# xboard.net
KiCad netlist of a schematic drawn in EAGLE
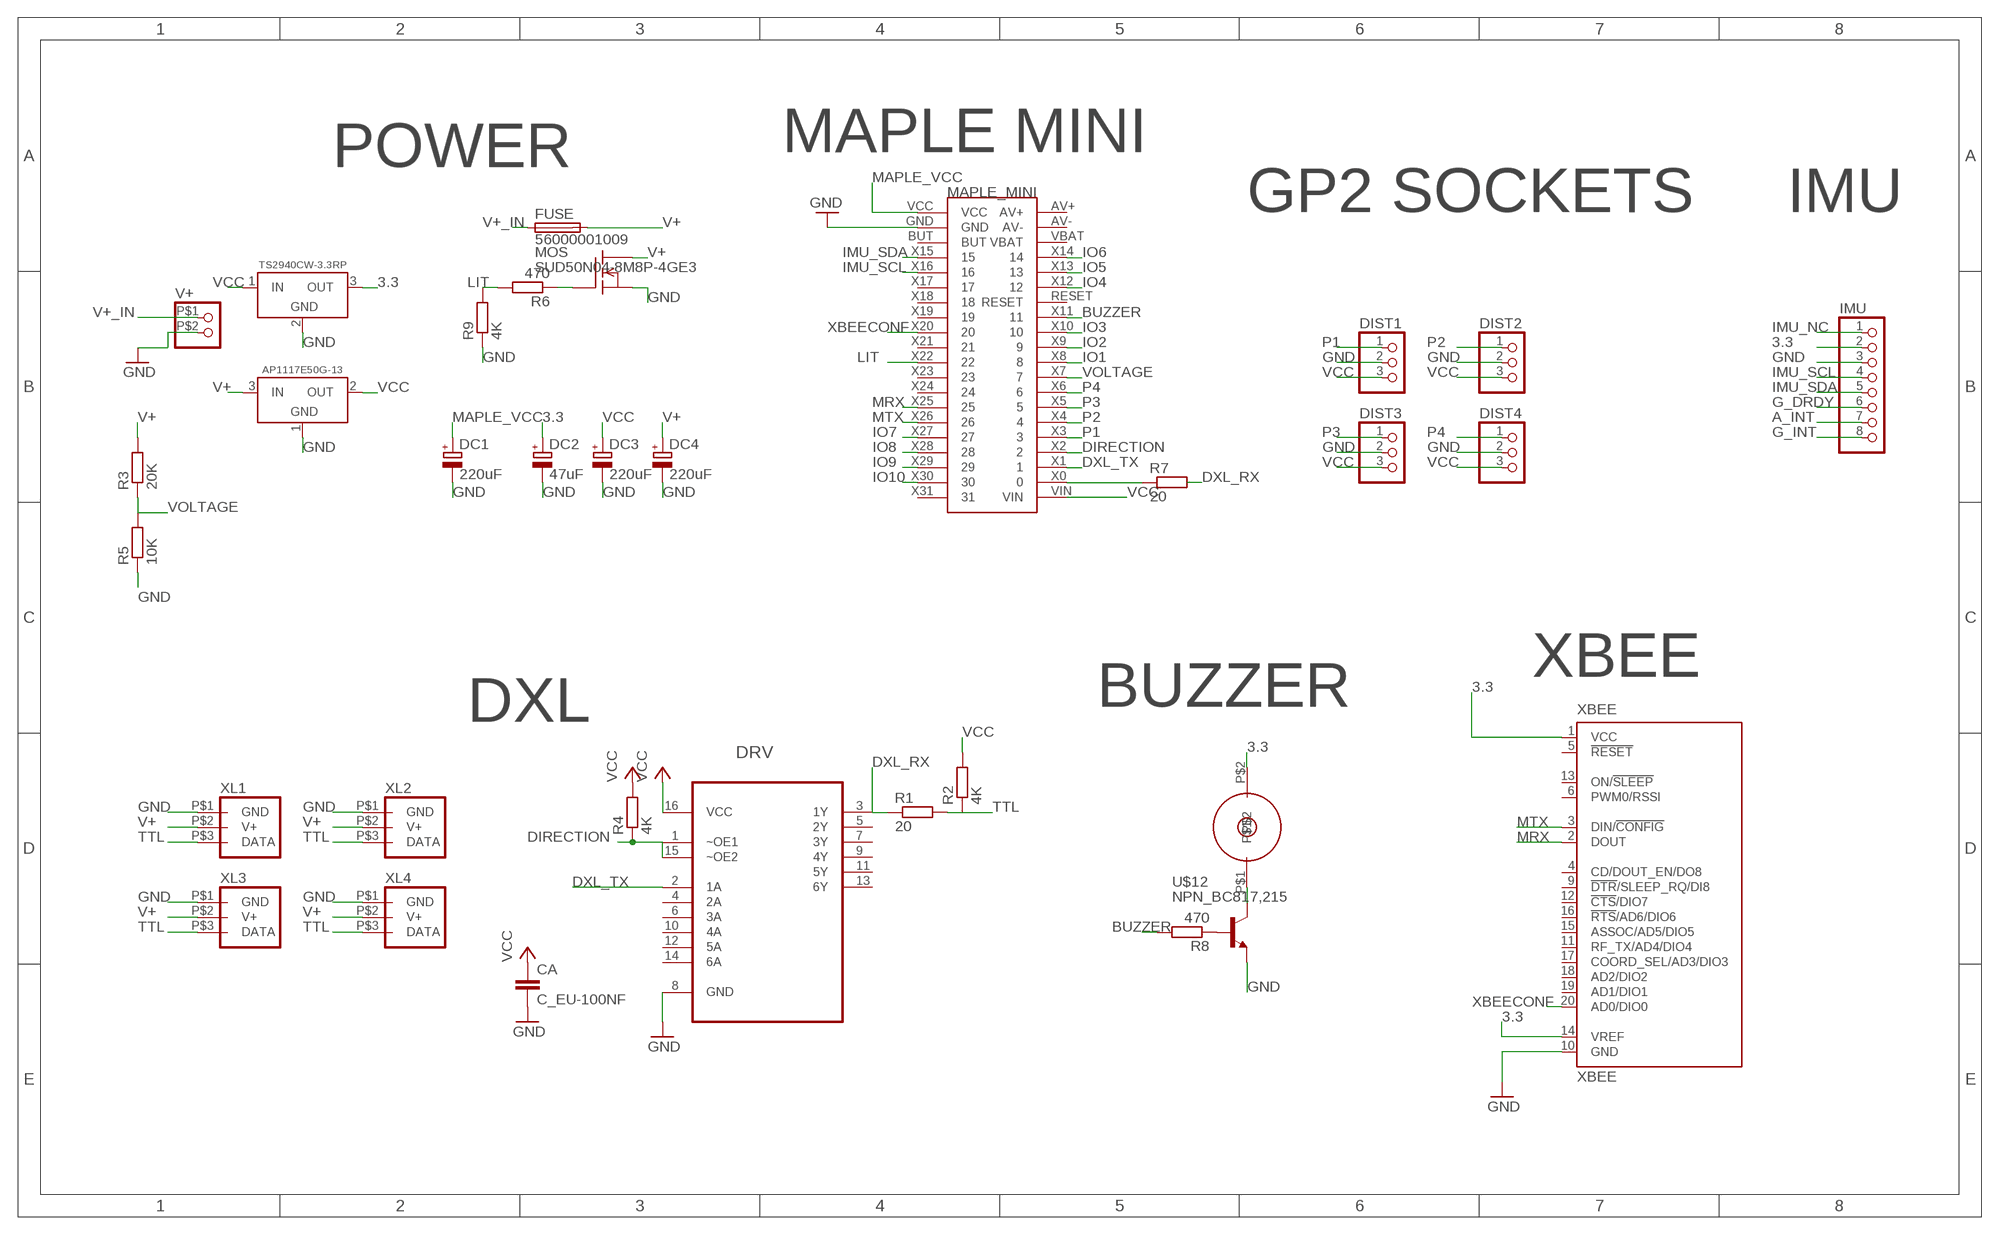
[diagram p0: schematic, sheet 1]

(export (version "E")
  (design (tool "Eeschema 10.0.6"))
  (components
    (comp (ref "BUZZER")
      (value "BUZZER66")
      (footprint "eagle-import:BUZZER66")
      (libsource (lib "eagle-import") (part "BUZZER66"))
    )
    (comp (ref "CA")
      (value "C_EU-100NF")
      (footprint "eagle-import:C0805")
      (libsource (lib "eagle-import") (part "C_EU-100NF"))
    )
    (comp (ref "DC1")
      (value "220uF")
      (footprint "eagle-import:PANASONIC_D8")
      (libsource (lib "eagle-import") (part "CPOL_EUPANASONIC_D8"))
    )
    (comp (ref "DC2")
      (value "47uF")
      (footprint "eagle-import:PANASONIC_D")
      (libsource (lib "eagle-import") (part "CPOL_EUPANASONIC_D"))
    )
    (comp (ref "DC3")
      (value "220uF")
      (footprint "eagle-import:PANASONIC_D8")
      (libsource (lib "eagle-import") (part "CPOL_EUPANASONIC_D8"))
    )
    (comp (ref "DC4")
      (value "220uF")
      (footprint "eagle-import:PANASONIC_D8")
      (libsource (lib "eagle-import") (part "CPOL_EUPANASONIC_D8"))
    )
    (comp (ref "DIST1")
      (value "CONNEC_1X03")
      (footprint "eagle-import:CONNEC_1X03")
      (libsource (lib "eagle-import") (part "CONNEC_1X03"))
    )
    (comp (ref "DIST2")
      (value "CONNEC_1X03")
      (footprint "eagle-import:CONNEC_1X03")
      (libsource (lib "eagle-import") (part "CONNEC_1X03"))
    )
    (comp (ref "DIST3")
      (value "CONNEC_1X03")
      (footprint "eagle-import:CONNEC_1X03")
      (libsource (lib "eagle-import") (part "CONNEC_1X03"))
    )
    (comp (ref "DIST4")
      (value "CONNEC_1X03")
      (footprint "eagle-import:CONNEC_1X03")
      (libsource (lib "eagle-import") (part "CONNEC_1X03"))
    )
    (comp (ref "DRV")
      (value "CD74HCT367M")
      (footprint "eagle-import:SOIC127P600X175-16N")
      (libsource (lib "eagle-import") (part "CD74HCT367M"))
    )
    (comp (ref "FUSE")
      (value "56000001009")
      (footprint "eagle-import:56000001009")
      (libsource (lib "eagle-import") (part "56000001009"))
    )
    (comp (ref "IMU")
      (value "CONNEC_1X08")
      (footprint "eagle-import:CONNEC_1X08")
      (libsource (lib "eagle-import") (part "CONNEC_1X08"))
    )
    (comp (ref "MAPLE_MINI")
      (value "MAPLE_MINI")
      (footprint "eagle-import:CONNEC_2X20")
      (libsource (lib "eagle-import") (part "MAPLE_MINI"))
    )
    (comp (ref "MOS")
      (value "SUD50N04-8M8P-4GE3")
      (footprint "eagle-import:TO252")
      (libsource (lib "eagle-import") (part "SUD50N04-8M8P-4GE3"))
    )
    (comp (ref "R1")
      (value "20")
      (footprint "eagle-import:R0805")
      (libsource (lib "eagle-import") (part "R-EU_R0805"))
    )
    (comp (ref "R2")
      (value "4K")
      (footprint "eagle-import:R0805")
      (libsource (lib "eagle-import") (part "R-EU_R0805"))
    )
    (comp (ref "R3")
      (value "20K")
      (footprint "eagle-import:R0805")
      (libsource (lib "eagle-import") (part "R-EU_R0805"))
    )
    (comp (ref "R4")
      (value "4K")
      (footprint "eagle-import:R0805")
      (libsource (lib "eagle-import") (part "RESISTANCE-R0805"))
    )
    (comp (ref "R5")
      (value "10K")
      (footprint "eagle-import:R0805")
      (libsource (lib "eagle-import") (part "R-EU_R0805"))
    )
    (comp (ref "R6")
      (value "470")
      (footprint "eagle-import:R0805")
      (libsource (lib "eagle-import") (part "R-EU_R0805"))
    )
    (comp (ref "R7")
      (value "20")
      (footprint "eagle-import:R0805")
      (libsource (lib "eagle-import") (part "R-EU_R0805"))
    )
    (comp (ref "R8")
      (value "470")
      (footprint "eagle-import:R0805")
      (libsource (lib "eagle-import") (part "R-EU_R0805"))
    )
    (comp (ref "R9")
      (value "4K")
      (footprint "eagle-import:R0805")
      (libsource (lib "eagle-import") (part "RESISTANCE-R0805"))
    )
    (comp (ref "U$7")
      (value "TS2940CW-3.3RP")
      (footprint "eagle-import:SOT223")
      (libsource (lib "eagle-import") (part "TS2940CW-3.3RP"))
    )
    (comp (ref "U$8")
      (value "AP1117E50G-13")
      (footprint "eagle-import:SOT223")
      (libsource (lib "eagle-import") (part "AP1117E50G-13"))
    )
    (comp (ref "U$12")
      (value "NPN_BC817,215")
      (footprint "eagle-import:SOT-23")
      (libsource (lib "eagle-import") (part "NPN_BC817,215"))
    )
    (comp (ref "V+")
      (value "CONNEC_1X02BIG")
      (footprint "eagle-import:CONNEC_1X02_BIG")
      (libsource (lib "eagle-import") (part "CONNEC_1X02BIG"))
    )
    (comp (ref "XBEE")
      (value "XBEE")
      (footprint "eagle-import:XBEE")
      (fields (field (name "MPN") "XBP24-Z7UIT-004"))
      (libsource (lib "eagle-import") (part "XBEE"))
    )
    (comp (ref "XL1")
      (value "XL_320_CONNEC")
      (footprint "eagle-import:DXL_320_CONNEC")
      (libsource (lib "eagle-import") (part "XL_320_CONNEC"))
    )
    (comp (ref "XL2")
      (value "XL_320_CONNEC")
      (footprint "eagle-import:DXL_320_CONNEC")
      (libsource (lib "eagle-import") (part "XL_320_CONNEC"))
    )
    (comp (ref "XL3")
      (value "XL_320_CONNEC")
      (footprint "eagle-import:DXL_320_CONNEC")
      (libsource (lib "eagle-import") (part "XL_320_CONNEC"))
    )
    (comp (ref "XL4")
      (value "XL_320_CONNEC")
      (footprint "eagle-import:DXL_320_CONNEC")
      (libsource (lib "eagle-import") (part "XL_320_CONNEC"))
    )
  )
  (nets
    (net (code "1") (name "/3.3") (class "Default")
      (node (ref "BUZZER") (pin "P$2") (pinfunction "P$2_P$2") (pintype "bidirectional"))
      (node (ref "DC2") (pin "+") (pinfunction "+_+") (pintype "passive"))
      (node (ref "IMU") (pin "2") (pinfunction "2_2") (pintype "passive"))
      (node (ref "U$7") (pin "3") (pinfunction "OUT_3") (pintype "output"))
      (node (ref "XBEE") (pin "1") (pinfunction "VCC_1") (pintype "power_in"))
      (node (ref "XBEE") (pin "14") (pinfunction "VREF_14") (pintype "input"))
    )
    (net (code "2") (name "/A_INT") (class "Default")
      (node (ref "IMU") (pin "7") (pinfunction "7_7") (pintype "passive"))
    )
    (net (code "3") (name "/BUZZER") (class "Default")
      (node (ref "MAPLE_MINI") (pin "X11") (pinfunction "11_X11") (pintype "bidirectional"))
      (node (ref "R8") (pin "2") (pinfunction "2_2") (pintype "passive"))
    )
    (net (code "4") (name "/DIRECTION") (class "Default")
      (node (ref "DRV") (pin "1") (pinfunction "~{OE1}_1") (pintype "input"))
      (node (ref "DRV") (pin "15") (pinfunction "~{OE2}_15") (pintype "input"))
      (node (ref "MAPLE_MINI") (pin "X2") (pinfunction "2_X2") (pintype "bidirectional"))
      (node (ref "R4") (pin "1") (pinfunction "1_1") (pintype "passive"))
    )
    (net (code "5") (name "/DXL_RX") (class "Default")
      (node (ref "DRV") (pin "3") (pinfunction "1Y_3") (pintype "output"))
      (node (ref "R1") (pin "1") (pinfunction "1_1") (pintype "passive"))
      (node (ref "R7") (pin "2") (pinfunction "2_2") (pintype "passive"))
    )
    (net (code "6") (name "/DXL_TX") (class "Default")
      (node (ref "DRV") (pin "2") (pinfunction "1A_2") (pintype "input"))
      (node (ref "MAPLE_MINI") (pin "X1") (pinfunction "1_X1") (pintype "bidirectional"))
    )
    (net (code "7") (name "/G_DRDY") (class "Default")
      (node (ref "IMU") (pin "6") (pinfunction "6_6") (pintype "passive"))
    )
    (net (code "8") (name "/G_INT") (class "Default")
      (node (ref "IMU") (pin "8") (pinfunction "8_8") (pintype "passive"))
    )
    (net (code "9") (name "/IMU_NC") (class "Default")
      (node (ref "IMU") (pin "1") (pinfunction "1_1") (pintype "passive"))
    )
    (net (code "10") (name "/IMU_SCL") (class "Default")
      (node (ref "IMU") (pin "4") (pinfunction "4_4") (pintype "passive"))
      (node (ref "MAPLE_MINI") (pin "X16") (pinfunction "16_X16") (pintype "bidirectional"))
    )
    (net (code "11") (name "/IMU_SDA") (class "Default")
      (node (ref "IMU") (pin "5") (pinfunction "5_5") (pintype "passive"))
      (node (ref "MAPLE_MINI") (pin "X15") (pinfunction "15_X15") (pintype "bidirectional"))
    )
    (net (code "12") (name "/IO1") (class "Default")
      (node (ref "MAPLE_MINI") (pin "X8") (pinfunction "8_X8") (pintype "bidirectional"))
    )
    (net (code "13") (name "/IO2") (class "Default")
      (node (ref "MAPLE_MINI") (pin "X9") (pinfunction "9_X9") (pintype "bidirectional"))
    )
    (net (code "14") (name "/IO3") (class "Default")
      (node (ref "MAPLE_MINI") (pin "X10") (pinfunction "10_X10") (pintype "bidirectional"))
    )
    (net (code "15") (name "/IO4") (class "Default")
      (node (ref "MAPLE_MINI") (pin "X12") (pinfunction "12_X12") (pintype "bidirectional"))
    )
    (net (code "16") (name "/IO5") (class "Default")
      (node (ref "MAPLE_MINI") (pin "X13") (pinfunction "13_X13") (pintype "bidirectional"))
    )
    (net (code "17") (name "/IO6") (class "Default")
      (node (ref "MAPLE_MINI") (pin "X14") (pinfunction "14_X14") (pintype "bidirectional"))
    )
    (net (code "18") (name "/IO7") (class "Default")
      (node (ref "MAPLE_MINI") (pin "X27") (pinfunction "27_X27") (pintype "bidirectional"))
    )
    (net (code "19") (name "/IO8") (class "Default")
      (node (ref "MAPLE_MINI") (pin "X28") (pinfunction "28_X28") (pintype "bidirectional"))
    )
    (net (code "20") (name "/IO9") (class "Default")
      (node (ref "MAPLE_MINI") (pin "X29") (pinfunction "29_X29") (pintype "bidirectional"))
    )
    (net (code "21") (name "/IO10") (class "Default")
      (node (ref "MAPLE_MINI") (pin "X30") (pinfunction "30_X30") (pintype "bidirectional"))
    )
    (net (code "22") (name "/LIT") (class "Default")
      (node (ref "MAPLE_MINI") (pin "X22") (pinfunction "22_X22") (pintype "bidirectional"))
      (node (ref "R6") (pin "2") (pinfunction "2_2") (pintype "passive"))
      (node (ref "R9") (pin "2") (pinfunction "2_2") (pintype "passive"))
    )
    (net (code "23") (name "/MAPLE_VCC") (class "Default")
      (node (ref "DC1") (pin "+") (pinfunction "+_+") (pintype "passive"))
      (node (ref "MAPLE_MINI") (pin "VCC") (pinfunction "VCC_VCC") (pintype "bidirectional"))
    )
    (net (code "24") (name "/MRX") (class "Default")
      (node (ref "MAPLE_MINI") (pin "X25") (pinfunction "25_X25") (pintype "bidirectional"))
      (node (ref "XBEE") (pin "2") (pinfunction "DOUT_2") (pintype "output"))
    )
    (net (code "25") (name "/MTX") (class "Default")
      (node (ref "MAPLE_MINI") (pin "X26") (pinfunction "26_X26") (pintype "bidirectional"))
      (node (ref "XBEE") (pin "3") (pinfunction "DIN/~{CONFIG}_3") (pintype "input"))
    )
    (net (code "26") (name "/P1") (class "Default")
      (node (ref "DIST1") (pin "1") (pinfunction "1_1") (pintype "passive"))
      (node (ref "MAPLE_MINI") (pin "X3") (pinfunction "3_X3") (pintype "bidirectional"))
    )
    (net (code "27") (name "/P2") (class "Default")
      (node (ref "DIST2") (pin "1") (pinfunction "1_1") (pintype "passive"))
      (node (ref "MAPLE_MINI") (pin "X4") (pinfunction "4_X4") (pintype "bidirectional"))
    )
    (net (code "28") (name "/P3") (class "Default")
      (node (ref "DIST3") (pin "1") (pinfunction "1_1") (pintype "passive"))
      (node (ref "MAPLE_MINI") (pin "X5") (pinfunction "5_X5") (pintype "bidirectional"))
    )
    (net (code "29") (name "/P4") (class "Default")
      (node (ref "DIST4") (pin "1") (pinfunction "1_1") (pintype "passive"))
      (node (ref "MAPLE_MINI") (pin "X6") (pinfunction "6_X6") (pintype "bidirectional"))
    )
    (net (code "30") (name "/TTL") (class "Default")
      (node (ref "R1") (pin "2") (pinfunction "2_2") (pintype "passive"))
      (node (ref "R2") (pin "1") (pinfunction "1_1") (pintype "passive"))
      (node (ref "XL1") (pin "P$3") (pinfunction "DATA_P$3") (pintype "bidirectional"))
      (node (ref "XL2") (pin "P$3") (pinfunction "DATA_P$3") (pintype "bidirectional"))
      (node (ref "XL3") (pin "P$3") (pinfunction "DATA_P$3") (pintype "bidirectional"))
      (node (ref "XL4") (pin "P$3") (pinfunction "DATA_P$3") (pintype "bidirectional"))
    )
    (net (code "31") (name "/V+") (class "Default")
      (node (ref "DC4") (pin "+") (pinfunction "+_+") (pintype "passive"))
      (node (ref "FUSE") (pin "P$2") (pinfunction "2_P$2") (pintype "passive"))
      (node (ref "MOS") (pin "3") (pinfunction "D_3") (pintype "passive"))
      (node (ref "R3") (pin "2") (pinfunction "2_2") (pintype "passive"))
      (node (ref "U$8") (pin "3") (pinfunction "IN_3") (pintype "input"))
      (node (ref "XL1") (pin "P$2") (pinfunction "V+_P$2") (pintype "bidirectional"))
      (node (ref "XL2") (pin "P$2") (pinfunction "V+_P$2") (pintype "bidirectional"))
      (node (ref "XL3") (pin "P$2") (pinfunction "V+_P$2") (pintype "bidirectional"))
      (node (ref "XL4") (pin "P$2") (pinfunction "V+_P$2") (pintype "bidirectional"))
    )
    (net (code "32") (name "/V+_IN") (class "Default")
      (node (ref "FUSE") (pin "P$1") (pinfunction "1_P$1") (pintype "passive"))
      (node (ref "V+") (pin "P$1") (pinfunction "1_P$1") (pintype "passive"))
    )
    (net (code "33") (name "/VOLTAGE") (class "Default")
      (node (ref "MAPLE_MINI") (pin "X7") (pinfunction "7_X7") (pintype "bidirectional"))
      (node (ref "R3") (pin "1") (pinfunction "1_1") (pintype "passive"))
      (node (ref "R5") (pin "2") (pinfunction "2_2") (pintype "passive"))
    )
    (net (code "34") (name "/XBEECONF") (class "Default")
      (node (ref "MAPLE_MINI") (pin "X20") (pinfunction "20_X20") (pintype "bidirectional"))
      (node (ref "XBEE") (pin "20") (pinfunction "AD0/DIO0_20") (pintype "bidirectional"))
    )
    (net (code "35") (name "GND") (class "Default")
      (node (ref "CA") (pin "2") (pinfunction "2_2") (pintype "passive"))
      (node (ref "DC1") (pin "-") (pinfunction "-_-") (pintype "passive"))
      (node (ref "DC2") (pin "-") (pinfunction "-_-") (pintype "passive"))
      (node (ref "DC3") (pin "-") (pinfunction "-_-") (pintype "passive"))
      (node (ref "DC4") (pin "-") (pinfunction "-_-") (pintype "passive"))
      (node (ref "DIST1") (pin "2") (pinfunction "2_2") (pintype "passive"))
      (node (ref "DIST2") (pin "2") (pinfunction "2_2") (pintype "passive"))
      (node (ref "DIST3") (pin "2") (pinfunction "2_2") (pintype "passive"))
      (node (ref "DIST4") (pin "2") (pinfunction "2_2") (pintype "passive"))
      (node (ref "DRV") (pin "8") (pinfunction "GND_8") (pintype "passive"))
      (node (ref "IMU") (pin "3") (pinfunction "3_3") (pintype "passive"))
      (node (ref "MAPLE_MINI") (pin "GND") (pinfunction "GND_GND") (pintype "bidirectional"))
      (node (ref "MOS") (pin "2") (pinfunction "S_2") (pintype "passive"))
      (node (ref "R5") (pin "1") (pinfunction "1_1") (pintype "passive"))
      (node (ref "R9") (pin "1") (pinfunction "1_1") (pintype "passive"))
      (node (ref "U$12") (pin "2") (pinfunction "E_2") (pintype "passive"))
      (node (ref "U$7") (pin "2") (pinfunction "GND_2") (pintype "power_in"))
      (node (ref "U$8") (pin "1") (pinfunction "GND_1") (pintype "power_in"))
      (node (ref "V+") (pin "P$2") (pinfunction "2_P$2") (pintype "passive"))
      (node (ref "XBEE") (pin "10") (pinfunction "GND_10") (pintype "power_in"))
      (node (ref "XL1") (pin "P$1") (pinfunction "GND_P$1") (pintype "bidirectional"))
      (node (ref "XL2") (pin "P$1") (pinfunction "GND_P$1") (pintype "bidirectional"))
      (node (ref "XL3") (pin "P$1") (pinfunction "GND_P$1") (pintype "bidirectional"))
      (node (ref "XL4") (pin "P$1") (pinfunction "GND_P$1") (pintype "bidirectional"))
    )
    (net (code "36") (name "Net-(MAPLE_MINI-0)") (class "Default")
      (node (ref "MAPLE_MINI") (pin "X0") (pinfunction "0_X0") (pintype "bidirectional"))
      (node (ref "R7") (pin "1") (pinfunction "1_1") (pintype "passive"))
    )
    (net (code "37") (name "Net-(MOS-G)") (class "Default")
      (node (ref "MOS") (pin "1") (pinfunction "G_1") (pintype "passive"))
      (node (ref "R6") (pin "1") (pinfunction "1_1") (pintype "passive"))
    )
    (net (code "38") (name "Net-(U$12-B)") (class "Default")
      (node (ref "R8") (pin "1") (pinfunction "1_1") (pintype "passive"))
      (node (ref "U$12") (pin "1") (pinfunction "B_1") (pintype "passive"))
    )
    (net (code "39") (name "Net-(U$12-C)") (class "Default")
      (node (ref "BUZZER") (pin "P$1") (pinfunction "P$1_P$1") (pintype "bidirectional"))
      (node (ref "U$12") (pin "3") (pinfunction "C_3") (pintype "passive"))
    )
    (net (code "40") (name "VCC") (class "Default")
      (node (ref "CA") (pin "1") (pinfunction "1_1") (pintype "passive"))
      (node (ref "DC3") (pin "+") (pinfunction "+_+") (pintype "passive"))
      (node (ref "DIST1") (pin "3") (pinfunction "3_3") (pintype "passive"))
      (node (ref "DIST2") (pin "3") (pinfunction "3_3") (pintype "passive"))
      (node (ref "DIST3") (pin "3") (pinfunction "3_3") (pintype "passive"))
      (node (ref "DIST4") (pin "3") (pinfunction "3_3") (pintype "passive"))
      (node (ref "DRV") (pin "16") (pinfunction "VCC_16") (pintype "input"))
      (node (ref "MAPLE_MINI") (pin "VIN") (pinfunction "VIN_VIN") (pintype "bidirectional"))
      (node (ref "R2") (pin "2") (pinfunction "2_2") (pintype "passive"))
      (node (ref "R4") (pin "2") (pinfunction "2_2") (pintype "passive"))
      (node (ref "U$7") (pin "1") (pinfunction "IN_1") (pintype "input"))
      (node (ref "U$8") (pin "2") (pinfunction "OUT_2") (pintype "output"))
    )
    (net (code "41") (name "unconnected-(DRV-2A-Pad4)") (class "Default")
      (node (ref "DRV") (pin "4") (pinfunction "2A_4") (pintype "input"))
    )
    (net (code "42") (name "unconnected-(DRV-2Y-Pad5)") (class "Default")
      (node (ref "DRV") (pin "5") (pinfunction "2Y_5") (pintype "output"))
    )
    (net (code "43") (name "unconnected-(DRV-3A-Pad6)") (class "Default")
      (node (ref "DRV") (pin "6") (pinfunction "3A_6") (pintype "input"))
    )
    (net (code "44") (name "unconnected-(DRV-3Y-Pad7)") (class "Default")
      (node (ref "DRV") (pin "7") (pinfunction "3Y_7") (pintype "output"))
    )
    (net (code "45") (name "unconnected-(DRV-4A-Pad10)") (class "Default")
      (node (ref "DRV") (pin "10") (pinfunction "4A_10") (pintype "input"))
    )
    (net (code "46") (name "unconnected-(DRV-4Y-Pad9)") (class "Default")
      (node (ref "DRV") (pin "9") (pinfunction "4Y_9") (pintype "output"))
    )
    (net (code "47") (name "unconnected-(DRV-5A-Pad12)") (class "Default")
      (node (ref "DRV") (pin "12") (pinfunction "5A_12") (pintype "input"))
    )
    (net (code "48") (name "unconnected-(DRV-5Y-Pad11)") (class "Default")
      (node (ref "DRV") (pin "11") (pinfunction "5Y_11") (pintype "output"))
    )
    (net (code "49") (name "unconnected-(DRV-6A-Pad14)") (class "Default")
      (node (ref "DRV") (pin "14") (pinfunction "6A_14") (pintype "input"))
    )
    (net (code "50") (name "unconnected-(DRV-6Y-Pad13)") (class "Default")
      (node (ref "DRV") (pin "13") (pinfunction "6Y_13") (pintype "output"))
    )
    (net (code "51") (name "unconnected-(MAPLE_MINI-17-PadX17)") (class "Default")
      (node (ref "MAPLE_MINI") (pin "X17") (pinfunction "17_X17") (pintype "bidirectional"))
    )
    (net (code "52") (name "unconnected-(MAPLE_MINI-18-PadX18)") (class "Default")
      (node (ref "MAPLE_MINI") (pin "X18") (pinfunction "18_X18") (pintype "bidirectional"))
    )
    (net (code "53") (name "unconnected-(MAPLE_MINI-19-PadX19)") (class "Default")
      (node (ref "MAPLE_MINI") (pin "X19") (pinfunction "19_X19") (pintype "bidirectional"))
    )
    (net (code "54") (name "unconnected-(MAPLE_MINI-21-PadX21)") (class "Default")
      (node (ref "MAPLE_MINI") (pin "X21") (pinfunction "21_X21") (pintype "bidirectional"))
    )
    (net (code "55") (name "unconnected-(MAPLE_MINI-23-PadX23)") (class "Default")
      (node (ref "MAPLE_MINI") (pin "X23") (pinfunction "23_X23") (pintype "bidirectional"))
    )
    (net (code "56") (name "unconnected-(MAPLE_MINI-24-PadX24)") (class "Default")
      (node (ref "MAPLE_MINI") (pin "X24") (pinfunction "24_X24") (pintype "bidirectional"))
    )
    (net (code "57") (name "unconnected-(MAPLE_MINI-31-PadX31)") (class "Default")
      (node (ref "MAPLE_MINI") (pin "X31") (pinfunction "31_X31") (pintype "bidirectional"))
    )
    (net (code "58") (name "unconnected-(MAPLE_MINI-PadAV+)") (class "Default")
      (node (ref "MAPLE_MINI") (pin "AV+") (pinfunction "AV+_AV+") (pintype "bidirectional"))
    )
    (net (code "59") (name "unconnected-(MAPLE_MINI-PadAV-)") (class "Default")
      (node (ref "MAPLE_MINI") (pin "AV-") (pinfunction "AV-_AV-") (pintype "bidirectional"))
    )
    (net (code "60") (name "unconnected-(MAPLE_MINI-PadBUT)") (class "Default")
      (node (ref "MAPLE_MINI") (pin "BUT") (pinfunction "BUT_BUT") (pintype "bidirectional"))
    )
    (net (code "61") (name "unconnected-(MAPLE_MINI-PadRESET)") (class "Default")
      (node (ref "MAPLE_MINI") (pin "RESET") (pinfunction "RESET_RESET") (pintype "bidirectional"))
    )
    (net (code "62") (name "unconnected-(MAPLE_MINI-PadVBAT)") (class "Default")
      (node (ref "MAPLE_MINI") (pin "VBAT") (pinfunction "VBAT_VBAT") (pintype "bidirectional"))
    )
    (net (code "63") (name "unconnected-(XBEE-AD1{slash}DIO1-Pad19)") (class "Default")
      (node (ref "XBEE") (pin "19") (pinfunction "AD1/DIO1_19") (pintype "bidirectional"))
    )
    (net (code "64") (name "unconnected-(XBEE-AD2{slash}DIO2-Pad18)") (class "Default")
      (node (ref "XBEE") (pin "18") (pinfunction "AD2/DIO2_18") (pintype "bidirectional"))
    )
    (net (code "65") (name "unconnected-(XBEE-ASSOC{slash}AD5{slash}DIO5-Pad15)") (class "Default")
      (node (ref "XBEE") (pin "15") (pinfunction "ASSOC/AD5/DIO5_15") (pintype "bidirectional"))
    )
    (net (code "66") (name "unconnected-(XBEE-CD{slash}DOUT_EN{slash}DO8-Pad4)") (class "Default")
      (node (ref "XBEE") (pin "4") (pinfunction "CD/DOUT_EN/DO8_4") (pintype "output"))
    )
    (net (code "67") (name "unconnected-(XBEE-COORD_SEL{slash}AD3{slash}DIO3-Pad17)") (class "Default")
      (node (ref "XBEE") (pin "17") (pinfunction "COORD_SEL/AD3/DIO3_17") (pintype "bidirectional"))
    )
    (net (code "68") (name "unconnected-(XBEE-ON{slash}~{SLEEP}-Pad13)") (class "Default")
      (node (ref "XBEE") (pin "13") (pinfunction "ON/~{SLEEP}_13") (pintype "output"))
    )
    (net (code "69") (name "unconnected-(XBEE-PWM0{slash}RSSI-Pad6)") (class "Default")
      (node (ref "XBEE") (pin "6") (pinfunction "PWM0/RSSI_6") (pintype "output"))
    )
    (net (code "70") (name "unconnected-(XBEE-RF_TX{slash}AD4{slash}DIO4-Pad11)") (class "Default")
      (node (ref "XBEE") (pin "11") (pinfunction "RF_TX/AD4/DIO4_11") (pintype "bidirectional"))
    )
    (net (code "71") (name "unconnected-(XBEE-~{CTS}{slash}DIO7-Pad12)") (class "Default")
      (node (ref "XBEE") (pin "12") (pinfunction "~{CTS}/DIO7_12") (pintype "bidirectional"))
    )
    (net (code "72") (name "unconnected-(XBEE-~{DTR}{slash}SLEEP_RQ{slash}DI8-Pad9)") (class "Default")
      (node (ref "XBEE") (pin "9") (pinfunction "~{DTR}/SLEEP_RQ/DI8_9") (pintype "bidirectional"))
    )
    (net (code "73") (name "unconnected-(XBEE-~{RESET}-Pad5)") (class "Default")
      (node (ref "XBEE") (pin "5") (pinfunction "~{RESET}_5") (pintype "input"))
    )
    (net (code "74") (name "unconnected-(XBEE-~{RTS}{slash}AD6{slash}DIO6-Pad16)") (class "Default")
      (node (ref "XBEE") (pin "16") (pinfunction "~{RTS}/AD6/DIO6_16") (pintype "bidirectional"))
    )
  )
)
